# arduino_8i_8o_Shield.net
KiCad netlist of a schematic drawn in EAGLE
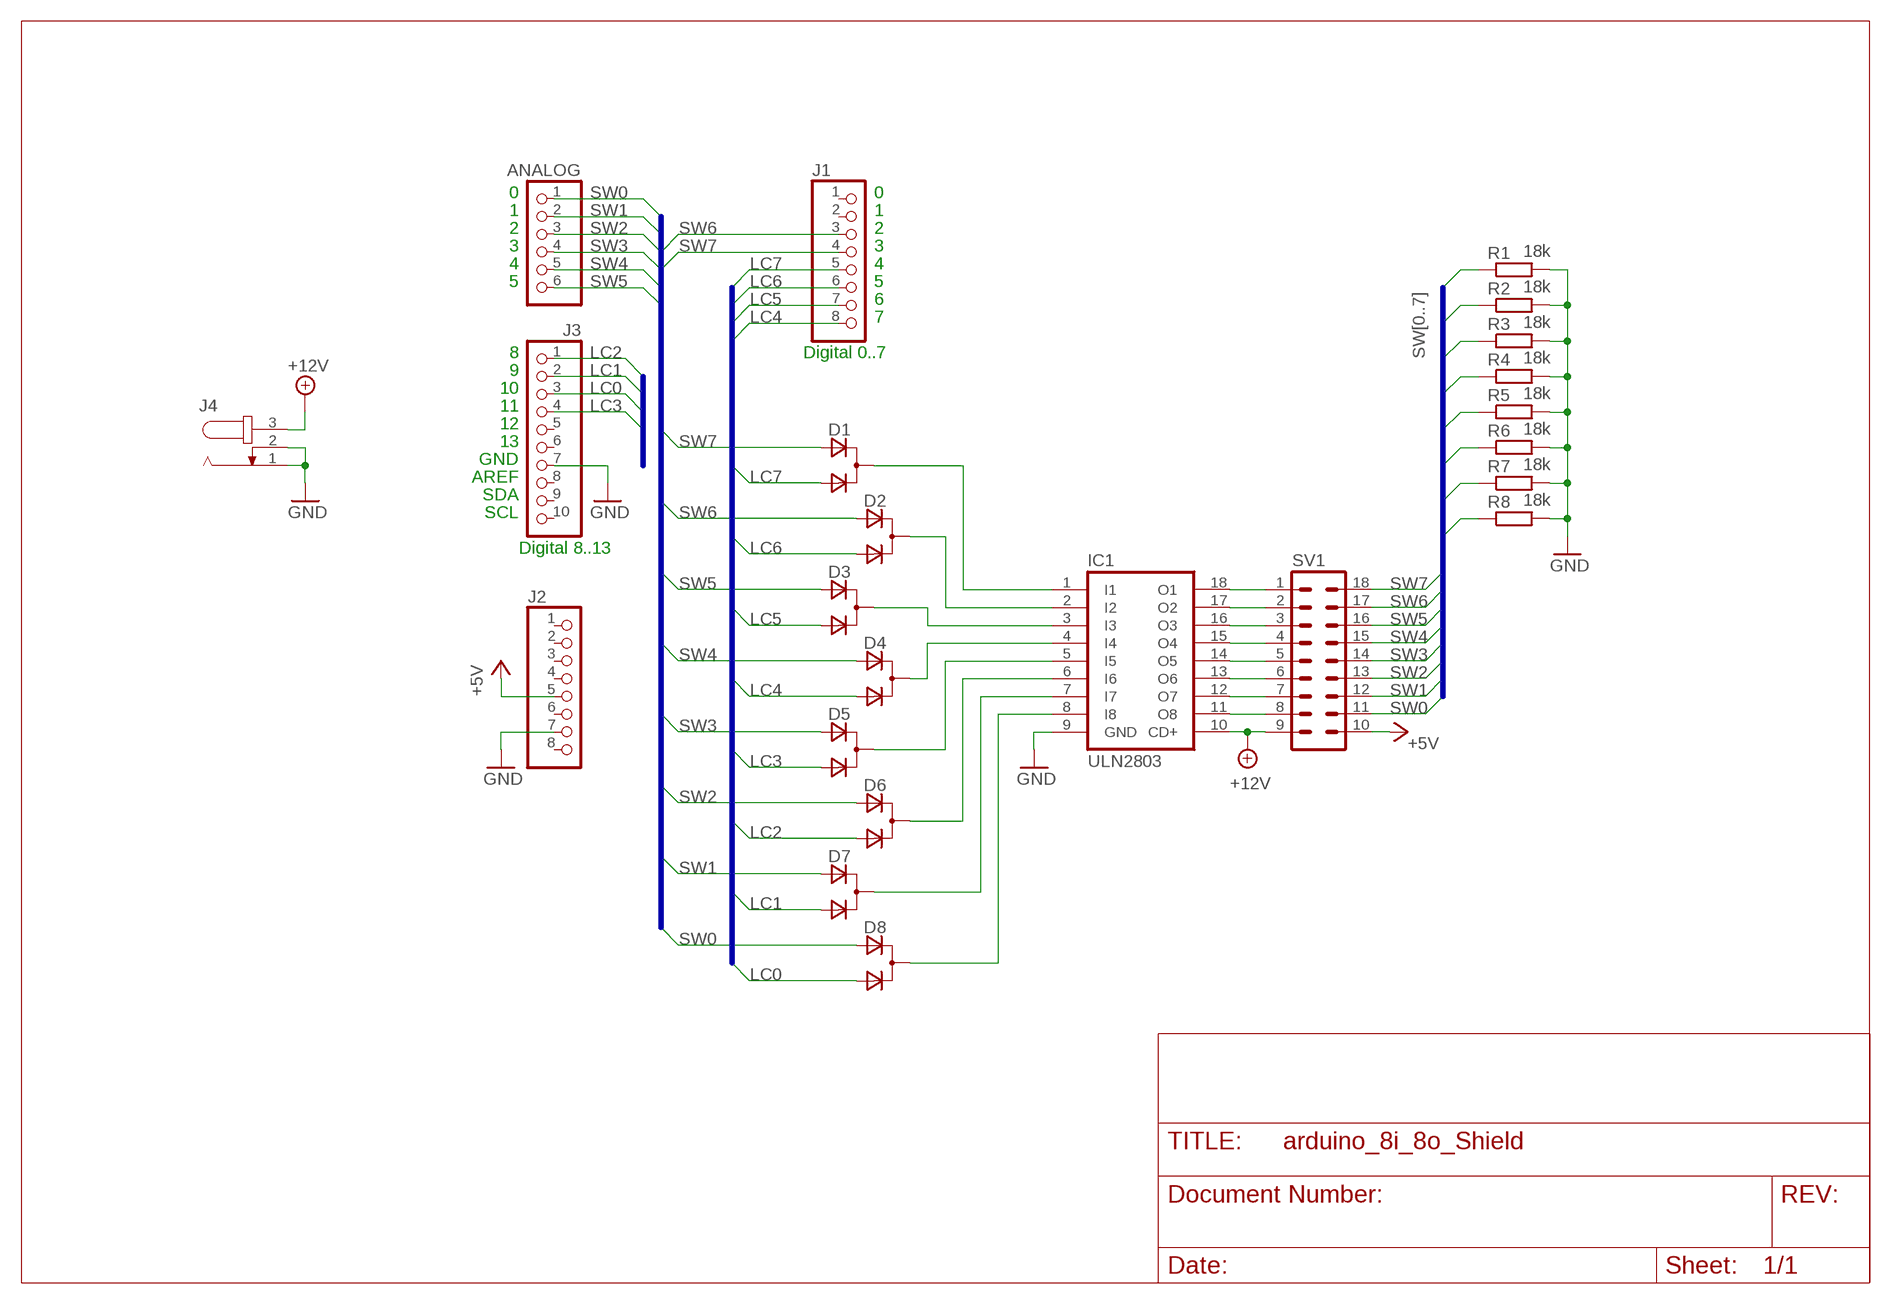
[diagram p0: schematic, sheet 1]

(export (version "E")
  (design (tool "Eeschema 10.0.6"))
  (components
    (comp (ref "ANALOG")
      (value "PINHD-1X6")
      (footprint "eagle-import:1X06")
      (libsource (lib "eagle-import") (part "PINHD-1X6"))
    )
    (comp (ref "D1")
      (value "VAR2_SOT23")
      (footprint "eagle-import:SOT-23")
      (libsource (lib "eagle-import") (part "VAR2_SOT23"))
    )
    (comp (ref "D2")
      (value "VAR2_SOT23")
      (footprint "eagle-import:SOT-23")
      (libsource (lib "eagle-import") (part "VAR2_SOT23"))
    )
    (comp (ref "D3")
      (value "VAR2_SOT23")
      (footprint "eagle-import:SOT-23")
      (libsource (lib "eagle-import") (part "VAR2_SOT23"))
    )
    (comp (ref "D4")
      (value "VAR2_SOT23")
      (footprint "eagle-import:SOT-23")
      (libsource (lib "eagle-import") (part "VAR2_SOT23"))
    )
    (comp (ref "D5")
      (value "VAR2_SOT23")
      (footprint "eagle-import:SOT-23")
      (libsource (lib "eagle-import") (part "VAR2_SOT23"))
    )
    (comp (ref "D6")
      (value "VAR2_SOT23")
      (footprint "eagle-import:SOT-23")
      (libsource (lib "eagle-import") (part "VAR2_SOT23"))
    )
    (comp (ref "D7")
      (value "VAR2_SOT23")
      (footprint "eagle-import:SOT-23")
      (libsource (lib "eagle-import") (part "VAR2_SOT23"))
    )
    (comp (ref "D8")
      (value "VAR2_SOT23")
      (footprint "eagle-import:SOT-23")
      (libsource (lib "eagle-import") (part "VAR2_SOT23"))
    )
    (comp (ref "IC1")
      (value "ULN2803")
      (footprint "eagle-import:DIL18")
      (libsource (lib "eagle-import") (part "ULN2803A"))
    )
    (comp (ref "J1")
      (value "PINHD-1X8TH")
      (footprint "eagle-import:1X08-TH")
      (libsource (lib "eagle-import") (part "PINHD-1X8TH"))
    )
    (comp (ref "J2")
      (value "PINHD-1X8TH")
      (footprint "eagle-import:1X08-TH")
      (libsource (lib "eagle-import") (part "PINHD-1X8TH"))
    )
    (comp (ref "J3")
      (value "PINHD-1X10TH")
      (footprint "eagle-import:1X10-TH")
      (libsource (lib "eagle-import") (part "PINHD-1X10TH"))
    )
    (comp (ref "J4")
      (value "JACK-PLUG0")
      (footprint "eagle-import:SPC4077")
      (libsource (lib "eagle-import") (part "JACK-PLUG0"))
    )
    (comp (ref "R1")
      (value "18k")
      (footprint "eagle-import:M1206")
      (libsource (lib "eagle-import") (part "R-EU_M1206"))
    )
    (comp (ref "R2")
      (value "18k")
      (footprint "eagle-import:M1206")
      (libsource (lib "eagle-import") (part "R-EU_M1206"))
    )
    (comp (ref "R3")
      (value "18k")
      (footprint "eagle-import:M1206")
      (libsource (lib "eagle-import") (part "R-EU_M1206"))
    )
    (comp (ref "R4")
      (value "18k")
      (footprint "eagle-import:M1206")
      (libsource (lib "eagle-import") (part "R-EU_M1206"))
    )
    (comp (ref "R5")
      (value "18k")
      (footprint "eagle-import:M1206")
      (libsource (lib "eagle-import") (part "R-EU_M1206"))
    )
    (comp (ref "R6")
      (value "18k")
      (footprint "eagle-import:M1206")
      (libsource (lib "eagle-import") (part "R-EU_M1206"))
    )
    (comp (ref "R7")
      (value "18k")
      (footprint "eagle-import:M1206")
      (libsource (lib "eagle-import") (part "R-EU_M1206"))
    )
    (comp (ref "R8")
      (value "18k")
      (footprint "eagle-import:M1206")
      (libsource (lib "eagle-import") (part "R-EU_M1206"))
    )
    (comp (ref "SV1")
      (value "IC18PL")
      (footprint "eagle-import:IC18PL")
      (libsource (lib "eagle-import") (part "IC18PL"))
    )
  )
  (nets
    (net (code "1") (name "+5V") (class "Default")
      (node (ref "J2") (pin "5") (pinfunction "5_5") (pintype "passive"))
      (node (ref "SV1") (pin "10") (pinfunction "10_10") (pintype "passive"))
    )
    (net (code "2") (name "+12V") (class "Default")
      (node (ref "IC1") (pin "10") (pinfunction "CD+_10") (pintype "passive"))
      (node (ref "J4") (pin "3") (pinfunction "3_3") (pintype "passive"))
      (node (ref "SV1") (pin "9") (pinfunction "9_9") (pintype "passive"))
    )
    (net (code "3") (name "/LC0") (class "Default")
      (node (ref "D8") (pin "3") (pinfunction "A2_3") (pintype "passive"))
      (node (ref "J3") (pin "3") (pinfunction "3_3") (pintype "passive"))
    )
    (net (code "4") (name "/LC1") (class "Default")
      (node (ref "D7") (pin "3") (pinfunction "A2_3") (pintype "passive"))
      (node (ref "J3") (pin "2") (pinfunction "2_2") (pintype "passive"))
    )
    (net (code "5") (name "/LC2") (class "Default")
      (node (ref "D6") (pin "3") (pinfunction "A2_3") (pintype "passive"))
      (node (ref "J3") (pin "1") (pinfunction "1_1") (pintype "passive"))
    )
    (net (code "6") (name "/LC3") (class "Default")
      (node (ref "D5") (pin "3") (pinfunction "A2_3") (pintype "passive"))
      (node (ref "J3") (pin "4") (pinfunction "4_4") (pintype "passive"))
    )
    (net (code "7") (name "/LC4") (class "Default")
      (node (ref "D4") (pin "3") (pinfunction "A2_3") (pintype "passive"))
      (node (ref "J1") (pin "8") (pinfunction "8_8") (pintype "passive"))
    )
    (net (code "8") (name "/LC5") (class "Default")
      (node (ref "D3") (pin "3") (pinfunction "A2_3") (pintype "passive"))
      (node (ref "J1") (pin "7") (pinfunction "7_7") (pintype "passive"))
    )
    (net (code "9") (name "/LC6") (class "Default")
      (node (ref "D2") (pin "3") (pinfunction "A2_3") (pintype "passive"))
      (node (ref "J1") (pin "6") (pinfunction "6_6") (pintype "passive"))
    )
    (net (code "10") (name "/LC7") (class "Default")
      (node (ref "D1") (pin "3") (pinfunction "A2_3") (pintype "passive"))
      (node (ref "J1") (pin "5") (pinfunction "5_5") (pintype "passive"))
    )
    (net (code "12") (name "/SW0") (class "Default")
      (node (ref "ANALOG") (pin "1") (pinfunction "1_1") (pintype "passive"))
      (node (ref "D8") (pin "2") (pinfunction "A1_2") (pintype "passive"))
      (node (ref "R1") (pin "1") (pinfunction "1_1") (pintype "passive"))
      (node (ref "SV1") (pin "11") (pinfunction "11_11") (pintype "passive"))
    )
    (net (code "13") (name "/SW1") (class "Default")
      (node (ref "ANALOG") (pin "2") (pinfunction "2_2") (pintype "passive"))
      (node (ref "D7") (pin "2") (pinfunction "A1_2") (pintype "passive"))
      (node (ref "R2") (pin "1") (pinfunction "1_1") (pintype "passive"))
      (node (ref "SV1") (pin "12") (pinfunction "12_12") (pintype "passive"))
    )
    (net (code "14") (name "/SW2") (class "Default")
      (node (ref "ANALOG") (pin "3") (pinfunction "3_3") (pintype "passive"))
      (node (ref "D6") (pin "2") (pinfunction "A1_2") (pintype "passive"))
      (node (ref "R3") (pin "1") (pinfunction "1_1") (pintype "passive"))
      (node (ref "SV1") (pin "13") (pinfunction "13_13") (pintype "passive"))
    )
    (net (code "15") (name "/SW3") (class "Default")
      (node (ref "ANALOG") (pin "4") (pinfunction "4_4") (pintype "passive"))
      (node (ref "D5") (pin "2") (pinfunction "A1_2") (pintype "passive"))
      (node (ref "R4") (pin "1") (pinfunction "1_1") (pintype "passive"))
      (node (ref "SV1") (pin "14") (pinfunction "14_14") (pintype "passive"))
    )
    (net (code "16") (name "/SW4") (class "Default")
      (node (ref "ANALOG") (pin "5") (pinfunction "5_5") (pintype "passive"))
      (node (ref "D4") (pin "2") (pinfunction "A1_2") (pintype "passive"))
      (node (ref "R5") (pin "1") (pinfunction "1_1") (pintype "passive"))
      (node (ref "SV1") (pin "15") (pinfunction "15_15") (pintype "passive"))
    )
    (net (code "17") (name "/SW5") (class "Default")
      (node (ref "ANALOG") (pin "6") (pinfunction "6_6") (pintype "passive"))
      (node (ref "D3") (pin "2") (pinfunction "A1_2") (pintype "passive"))
      (node (ref "R6") (pin "1") (pinfunction "1_1") (pintype "passive"))
      (node (ref "SV1") (pin "16") (pinfunction "16_16") (pintype "passive"))
    )
    (net (code "18") (name "/SW6") (class "Default")
      (node (ref "D2") (pin "2") (pinfunction "A1_2") (pintype "passive"))
      (node (ref "J1") (pin "3") (pinfunction "3_3") (pintype "passive"))
      (node (ref "R7") (pin "1") (pinfunction "1_1") (pintype "passive"))
      (node (ref "SV1") (pin "17") (pinfunction "17_17") (pintype "passive"))
    )
    (net (code "19") (name "/SW7") (class "Default")
      (node (ref "D1") (pin "2") (pinfunction "A1_2") (pintype "passive"))
      (node (ref "J1") (pin "4") (pinfunction "4_4") (pintype "passive"))
      (node (ref "R8") (pin "1") (pinfunction "1_1") (pintype "passive"))
      (node (ref "SV1") (pin "18") (pinfunction "18_18") (pintype "passive"))
    )
    (net (code "21") (name "GND") (class "Default")
      (node (ref "IC1") (pin "9") (pinfunction "GND_9") (pintype "power_in"))
      (node (ref "J2") (pin "7") (pinfunction "7_7") (pintype "passive"))
      (node (ref "J3") (pin "7") (pinfunction "7_7") (pintype "passive"))
      (node (ref "J4") (pin "1") (pinfunction "1_1") (pintype "passive"))
      (node (ref "J4") (pin "2") (pinfunction "2_2") (pintype "passive"))
      (node (ref "R1") (pin "2") (pinfunction "2_2") (pintype "passive"))
      (node (ref "R2") (pin "2") (pinfunction "2_2") (pintype "passive"))
      (node (ref "R3") (pin "2") (pinfunction "2_2") (pintype "passive"))
      (node (ref "R4") (pin "2") (pinfunction "2_2") (pintype "passive"))
      (node (ref "R5") (pin "2") (pinfunction "2_2") (pintype "passive"))
      (node (ref "R6") (pin "2") (pinfunction "2_2") (pintype "passive"))
      (node (ref "R7") (pin "2") (pinfunction "2_2") (pintype "passive"))
      (node (ref "R8") (pin "2") (pinfunction "2_2") (pintype "passive"))
    )
    (net (code "22") (name "Net-(D1-C)") (class "Default")
      (node (ref "D1") (pin "1") (pinfunction "C_1") (pintype "passive"))
      (node (ref "IC1") (pin "1") (pinfunction "I1_1") (pintype "input"))
    )
    (net (code "23") (name "Net-(D2-C)") (class "Default")
      (node (ref "D2") (pin "1") (pinfunction "C_1") (pintype "passive"))
      (node (ref "IC1") (pin "2") (pinfunction "I2_2") (pintype "input"))
    )
    (net (code "24") (name "Net-(D3-C)") (class "Default")
      (node (ref "D3") (pin "1") (pinfunction "C_1") (pintype "passive"))
      (node (ref "IC1") (pin "3") (pinfunction "I3_3") (pintype "input"))
    )
    (net (code "25") (name "Net-(D4-C)") (class "Default")
      (node (ref "D4") (pin "1") (pinfunction "C_1") (pintype "passive"))
      (node (ref "IC1") (pin "4") (pinfunction "I4_4") (pintype "input"))
    )
    (net (code "26") (name "Net-(D5-C)") (class "Default")
      (node (ref "D5") (pin "1") (pinfunction "C_1") (pintype "passive"))
      (node (ref "IC1") (pin "5") (pinfunction "I5_5") (pintype "input"))
    )
    (net (code "27") (name "Net-(D6-C)") (class "Default")
      (node (ref "D6") (pin "1") (pinfunction "C_1") (pintype "passive"))
      (node (ref "IC1") (pin "6") (pinfunction "I6_6") (pintype "input"))
    )
    (net (code "28") (name "Net-(D7-C)") (class "Default")
      (node (ref "D7") (pin "1") (pinfunction "C_1") (pintype "passive"))
      (node (ref "IC1") (pin "7") (pinfunction "I7_7") (pintype "input"))
    )
    (net (code "29") (name "Net-(D8-C)") (class "Default")
      (node (ref "D8") (pin "1") (pinfunction "C_1") (pintype "passive"))
      (node (ref "IC1") (pin "8") (pinfunction "I8_8") (pintype "input"))
    )
    (net (code "30") (name "Net-(IC1-O1)") (class "Default")
      (node (ref "IC1") (pin "18") (pinfunction "O1_18") (pintype "open_collector"))
      (node (ref "SV1") (pin "1") (pinfunction "1_1") (pintype "passive"))
    )
    (net (code "31") (name "Net-(IC1-O2)") (class "Default")
      (node (ref "IC1") (pin "17") (pinfunction "O2_17") (pintype "open_collector"))
      (node (ref "SV1") (pin "2") (pinfunction "2_2") (pintype "passive"))
    )
    (net (code "32") (name "Net-(IC1-O3)") (class "Default")
      (node (ref "IC1") (pin "16") (pinfunction "O3_16") (pintype "open_collector"))
      (node (ref "SV1") (pin "3") (pinfunction "3_3") (pintype "passive"))
    )
    (net (code "33") (name "Net-(IC1-O4)") (class "Default")
      (node (ref "IC1") (pin "15") (pinfunction "O4_15") (pintype "open_collector"))
      (node (ref "SV1") (pin "4") (pinfunction "4_4") (pintype "passive"))
    )
    (net (code "34") (name "Net-(IC1-O5)") (class "Default")
      (node (ref "IC1") (pin "14") (pinfunction "O5_14") (pintype "open_collector"))
      (node (ref "SV1") (pin "5") (pinfunction "5_5") (pintype "passive"))
    )
    (net (code "35") (name "Net-(IC1-O6)") (class "Default")
      (node (ref "IC1") (pin "13") (pinfunction "O6_13") (pintype "open_collector"))
      (node (ref "SV1") (pin "6") (pinfunction "6_6") (pintype "passive"))
    )
    (net (code "36") (name "Net-(IC1-O7)") (class "Default")
      (node (ref "IC1") (pin "12") (pinfunction "O7_12") (pintype "open_collector"))
      (node (ref "SV1") (pin "7") (pinfunction "7_7") (pintype "passive"))
    )
    (net (code "37") (name "Net-(IC1-O8)") (class "Default")
      (node (ref "IC1") (pin "11") (pinfunction "O8_11") (pintype "open_collector"))
      (node (ref "SV1") (pin "8") (pinfunction "8_8") (pintype "passive"))
    )
    (net (code "38") (name "unconnected-(J1-Pad1)") (class "Default")
      (node (ref "J1") (pin "1") (pinfunction "1_1") (pintype "passive"))
    )
    (net (code "39") (name "unconnected-(J1-Pad2)") (class "Default")
      (node (ref "J1") (pin "2") (pinfunction "2_2") (pintype "passive"))
    )
    (net (code "40") (name "unconnected-(J2-Pad1)") (class "Default")
      (node (ref "J2") (pin "1") (pinfunction "1_1") (pintype "passive"))
    )
    (net (code "41") (name "unconnected-(J2-Pad2)") (class "Default")
      (node (ref "J2") (pin "2") (pinfunction "2_2") (pintype "passive"))
    )
    (net (code "42") (name "unconnected-(J2-Pad3)") (class "Default")
      (node (ref "J2") (pin "3") (pinfunction "3_3") (pintype "passive"))
    )
    (net (code "43") (name "unconnected-(J2-Pad4)") (class "Default")
      (node (ref "J2") (pin "4") (pinfunction "4_4") (pintype "passive"))
    )
    (net (code "44") (name "unconnected-(J2-Pad6)") (class "Default")
      (node (ref "J2") (pin "6") (pinfunction "6_6") (pintype "passive"))
    )
    (net (code "45") (name "unconnected-(J2-Pad8)") (class "Default")
      (node (ref "J2") (pin "8") (pinfunction "8_8") (pintype "passive"))
    )
    (net (code "46") (name "unconnected-(J3-Pad5)") (class "Default")
      (node (ref "J3") (pin "5") (pinfunction "5_5") (pintype "passive"))
    )
    (net (code "47") (name "unconnected-(J3-Pad6)") (class "Default")
      (node (ref "J3") (pin "6") (pinfunction "6_6") (pintype "passive"))
    )
    (net (code "48") (name "unconnected-(J3-Pad8)") (class "Default")
      (node (ref "J3") (pin "8") (pinfunction "8_8") (pintype "passive"))
    )
    (net (code "49") (name "unconnected-(J3-Pad9)") (class "Default")
      (node (ref "J3") (pin "9") (pinfunction "9_9") (pintype "passive"))
    )
    (net (code "50") (name "unconnected-(J3-Pad10)") (class "Default")
      (node (ref "J3") (pin "10") (pinfunction "10_10") (pintype "passive"))
    )
  )
)
